# compiegne_v2.net
KiCad netlist of a schematic drawn in EAGLE
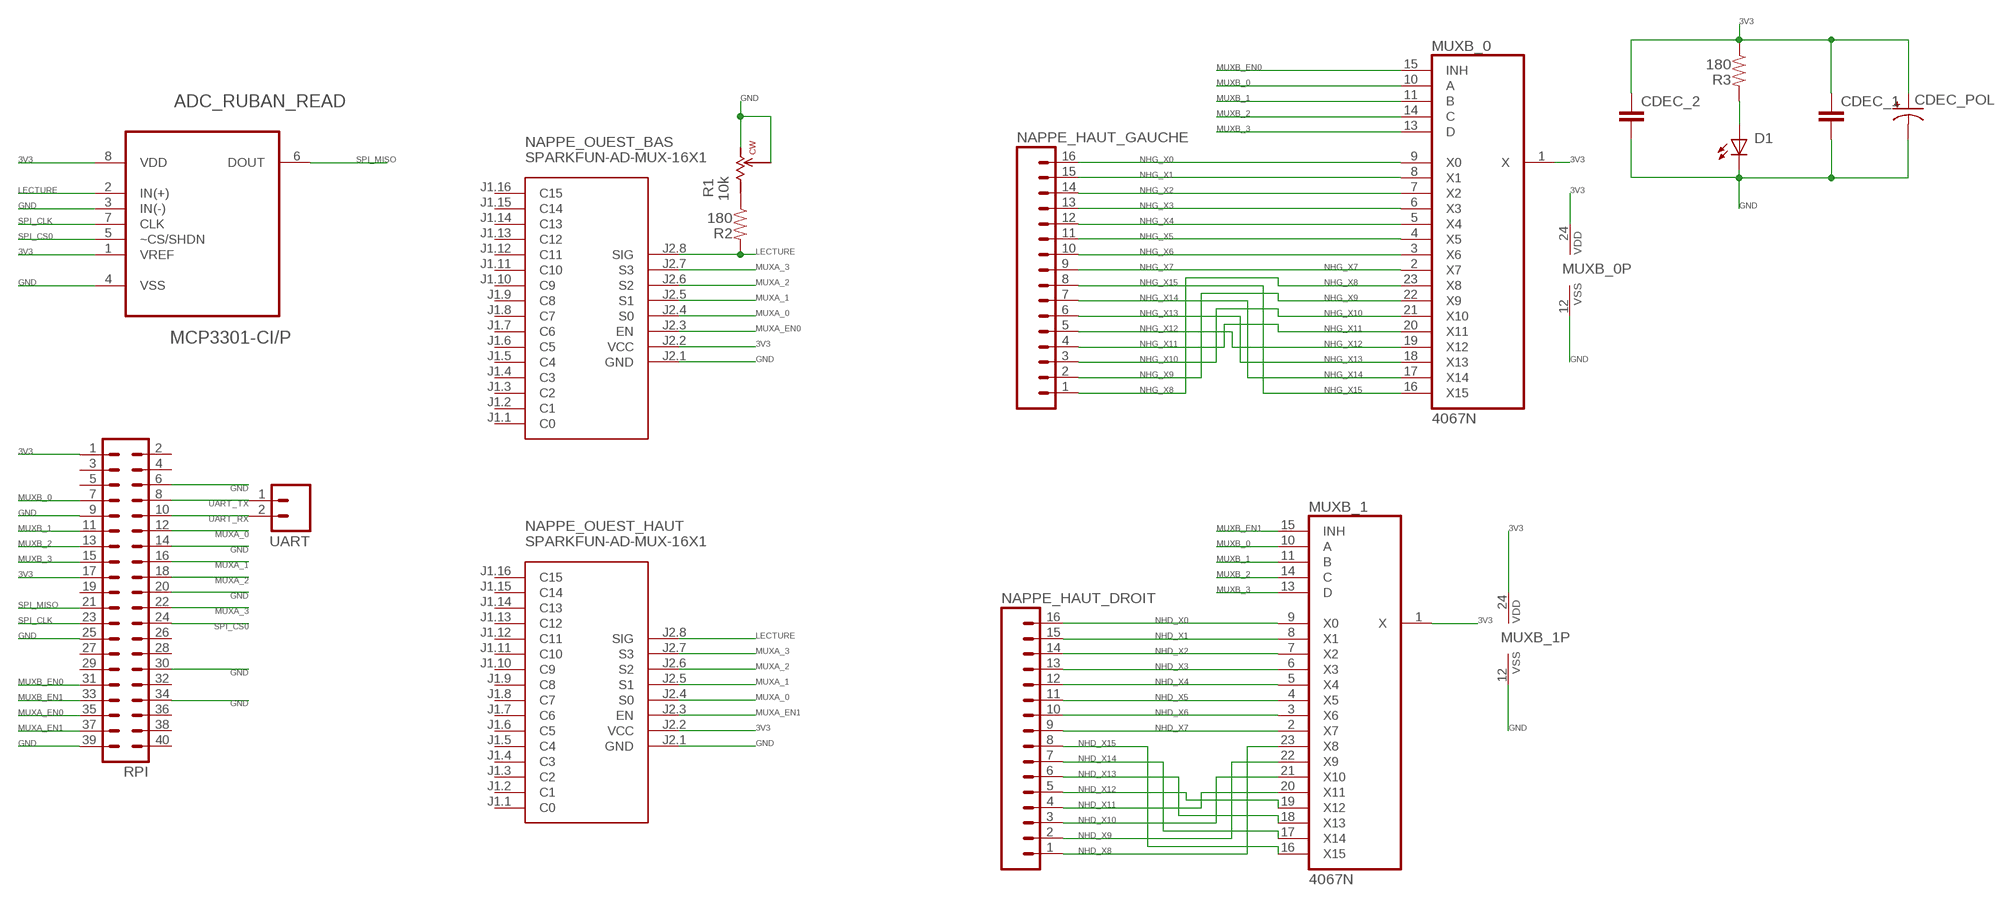
[diagram p0: schematic, sheet 1]

(export (version "E")
  (design (tool "Eeschema 10.0.6"))
  (components
    (comp (ref "ADC_RUBAN_READ")
      (value "MCP3301-CI/P")
      (footprint "eagle-import:DIP254P762X432-8")
      (libsource (lib "eagle-import") (part "MCP3301-CI/P"))
    )
    (comp (ref "CDEC_1")
      (value "PASSIF-CAP-PTH")
      (footprint "eagle-import:CAP-PTH")
      (libsource (lib "eagle-import") (part "PASSIF-CAP-PTH"))
    )
    (comp (ref "CDEC_2")
      (value "PASSIF-CAP-PTH")
      (footprint "eagle-import:CAP-PTH")
      (libsource (lib "eagle-import") (part "PASSIF-CAP-PTH"))
    )
    (comp (ref "CDEC_POL")
      (value "PASSIF-CAP_POL-TANTALUM-PTH")
      (footprint "eagle-import:CAP_POL-TANTALUM-PTH")
      (libsource (lib "eagle-import") (part "PASSIF-CAP_POL-TANTALUM-PTH"))
    )
    (comp (ref "D1")
      (value "LED-3MM")
      (footprint "eagle-import:3MM-LED")
      (libsource (lib "eagle-import") (part "LED-3MM"))
    )
    (comp (ref "MUXB_0")
      (value "4067N")
      (footprint "eagle-import:DIL24-6")
      (libsource (lib "eagle-import") (part "4067N"))
    )
    (comp (ref "MUXB_1")
      (value "4067N")
      (footprint "eagle-import:DIL24-6")
      (libsource (lib "eagle-import") (part "4067N"))
    )
    (comp (ref "NAPPE_HAUT_DROIT")
      (value "MA16")
      (footprint "eagle-import:16PA")
      (libsource (lib "eagle-import") (part "MA16"))
    )
    (comp (ref "NAPPE_HAUT_GAUCHE")
      (value "MA16")
      (footprint "eagle-import:16PA")
      (libsource (lib "eagle-import") (part "MA16"))
    )
    (comp (ref "NAPPE_OUEST_BAS")
      (value "SPARKFUN-AD-MUX-16X1")
      (footprint "eagle-import:SPARKFUN-AD-MUX-16X1")
      (libsource (lib "eagle-import") (part "SPARKFUN-AD-MUX-16X1"))
    )
    (comp (ref "NAPPE_OUEST_HAUT")
      (value "SPARKFUN-AD-MUX-16X1")
      (footprint "eagle-import:SPARKFUN-AD-MUX-16X1")
      (libsource (lib "eagle-import") (part "SPARKFUN-AD-MUX-16X1"))
    )
    (comp (ref "R1")
      (value "10k")
      (footprint "eagle-import:TRIMPOT_3266")
      (libsource (lib "eagle-import") (part "TRIMPOT_3266"))
    )
    (comp (ref "R2")
      (value "180")
      (footprint "eagle-import:RESISTOR-PTH")
      (libsource (lib "eagle-import") (part "PASSIF-RESISTOR-PTH"))
    )
    (comp (ref "R3")
      (value "180")
      (footprint "eagle-import:RESISTOR-PTH")
      (libsource (lib "eagle-import") (part "PASSIF-RESISTOR-PTH"))
    )
    (comp (ref "RPI")
      (value "MA20-2")
      (footprint "eagle-import:MA20-2")
      (libsource (lib "eagle-import") (part "MA20-2"))
    )
    (comp (ref "UART")
      (value "MA02")
      (footprint "eagle-import:02PA")
      (libsource (lib "eagle-import") (part "MA02"))
    )
  )
  (nets
    (net (code "1") (name "/3V3") (class "Default")
      (node (ref "ADC_RUBAN_READ") (pin "1") (pinfunction "VREF_1") (pintype "input"))
      (node (ref "ADC_RUBAN_READ") (pin "8") (pinfunction "VDD_8") (pintype "power_in"))
      (node (ref "CDEC_1") (pin "P$1") (pinfunction "1_P$1") (pintype "passive"))
      (node (ref "CDEC_2") (pin "P$1") (pinfunction "1_P$1") (pintype "passive"))
      (node (ref "CDEC_POL") (pin "+") (pinfunction "+_+") (pintype "passive"))
      (node (ref "MUXB_0") (pin "1") (pinfunction "X_1") (pintype "output"))
      (node (ref "MUXB_0") (pin "24") (pinfunction "VDD_24") (pintype "power_in"))
      (node (ref "MUXB_1") (pin "1") (pinfunction "X_1") (pintype "output"))
      (node (ref "MUXB_1") (pin "24") (pinfunction "VDD_24") (pintype "power_in"))
      (node (ref "NAPPE_OUEST_BAS") (pin "J2.2") (pinfunction "VCC_J2.2") (pintype "power_in"))
      (node (ref "NAPPE_OUEST_HAUT") (pin "J2.2") (pinfunction "VCC_J2.2") (pintype "power_in"))
      (node (ref "R3") (pin "P$1") (pinfunction "1_P$1") (pintype "passive"))
      (node (ref "RPI") (pin "1") (pinfunction "1_1") (pintype "passive"))
      (node (ref "RPI") (pin "17") (pinfunction "17_17") (pintype "passive"))
    )
    (net (code "2") (name "/GND") (class "Default")
      (node (ref "ADC_RUBAN_READ") (pin "3") (pinfunction "IN(-)_3") (pintype "input"))
      (node (ref "ADC_RUBAN_READ") (pin "4") (pinfunction "VSS_4") (pintype "passive"))
      (node (ref "CDEC_1") (pin "P$2") (pinfunction "2_P$2") (pintype "passive"))
      (node (ref "CDEC_2") (pin "P$2") (pinfunction "2_P$2") (pintype "passive"))
      (node (ref "CDEC_POL") (pin "-") (pinfunction "-_-") (pintype "passive"))
      (node (ref "D1") (pin "C") (pinfunction "C_C") (pintype "passive"))
      (node (ref "MUXB_0") (pin "12") (pinfunction "VSS_12") (pintype "power_in"))
      (node (ref "MUXB_1") (pin "12") (pinfunction "VSS_12") (pintype "power_in"))
      (node (ref "NAPPE_OUEST_BAS") (pin "J2.1") (pinfunction "GND_J2.1") (pintype "power_in"))
      (node (ref "NAPPE_OUEST_HAUT") (pin "J2.1") (pinfunction "GND_J2.1") (pintype "power_in"))
      (node (ref "R1") (pin "2") (pinfunction "2_2") (pintype "passive"))
      (node (ref "R1") (pin "3") (pinfunction "3_3") (pintype "passive"))
      (node (ref "RPI") (pin "14") (pinfunction "14_14") (pintype "passive"))
      (node (ref "RPI") (pin "20") (pinfunction "20_20") (pintype "passive"))
      (node (ref "RPI") (pin "25") (pinfunction "25_25") (pintype "passive"))
      (node (ref "RPI") (pin "30") (pinfunction "30_30") (pintype "passive"))
      (node (ref "RPI") (pin "34") (pinfunction "34_34") (pintype "passive"))
      (node (ref "RPI") (pin "39") (pinfunction "39_39") (pintype "passive"))
      (node (ref "RPI") (pin "6") (pinfunction "6_6") (pintype "passive"))
      (node (ref "RPI") (pin "9") (pinfunction "9_9") (pintype "passive"))
    )
    (net (code "3") (name "/LECTURE") (class "Default")
      (node (ref "ADC_RUBAN_READ") (pin "2") (pinfunction "IN(+)_2") (pintype "input"))
      (node (ref "NAPPE_OUEST_BAS") (pin "J2.8") (pinfunction "SIG_J2.8") (pintype "bidirectional"))
      (node (ref "NAPPE_OUEST_HAUT") (pin "J2.8") (pinfunction "SIG_J2.8") (pintype "bidirectional"))
      (node (ref "R2") (pin "P$2") (pinfunction "2_P$2") (pintype "passive"))
    )
    (net (code "4") (name "/MUXA_0") (class "Default")
      (node (ref "NAPPE_OUEST_BAS") (pin "J2.4") (pinfunction "S0_J2.4") (pintype "bidirectional"))
      (node (ref "NAPPE_OUEST_HAUT") (pin "J2.4") (pinfunction "S0_J2.4") (pintype "bidirectional"))
      (node (ref "RPI") (pin "12") (pinfunction "12_12") (pintype "passive"))
    )
    (net (code "5") (name "/MUXA_1") (class "Default")
      (node (ref "NAPPE_OUEST_BAS") (pin "J2.5") (pinfunction "S1_J2.5") (pintype "bidirectional"))
      (node (ref "NAPPE_OUEST_HAUT") (pin "J2.5") (pinfunction "S1_J2.5") (pintype "bidirectional"))
      (node (ref "RPI") (pin "16") (pinfunction "16_16") (pintype "passive"))
    )
    (net (code "6") (name "/MUXA_2") (class "Default")
      (node (ref "NAPPE_OUEST_BAS") (pin "J2.6") (pinfunction "S2_J2.6") (pintype "bidirectional"))
      (node (ref "NAPPE_OUEST_HAUT") (pin "J2.6") (pinfunction "S2_J2.6") (pintype "bidirectional"))
      (node (ref "RPI") (pin "18") (pinfunction "18_18") (pintype "passive"))
    )
    (net (code "7") (name "/MUXA_3") (class "Default")
      (node (ref "NAPPE_OUEST_BAS") (pin "J2.7") (pinfunction "S3_J2.7") (pintype "bidirectional"))
      (node (ref "NAPPE_OUEST_HAUT") (pin "J2.7") (pinfunction "S3_J2.7") (pintype "bidirectional"))
      (node (ref "RPI") (pin "22") (pinfunction "22_22") (pintype "passive"))
    )
    (net (code "8") (name "/MUXA_EN0") (class "Default")
      (node (ref "NAPPE_OUEST_BAS") (pin "J2.3") (pinfunction "EN_J2.3") (pintype "input"))
      (node (ref "RPI") (pin "35") (pinfunction "35_35") (pintype "passive"))
    )
    (net (code "9") (name "/MUXA_EN1") (class "Default")
      (node (ref "NAPPE_OUEST_HAUT") (pin "J2.3") (pinfunction "EN_J2.3") (pintype "input"))
      (node (ref "RPI") (pin "37") (pinfunction "37_37") (pintype "passive"))
    )
    (net (code "10") (name "/MUXB_0") (class "Default")
      (node (ref "MUXB_0") (pin "10") (pinfunction "A_10") (pintype "input"))
      (node (ref "MUXB_1") (pin "10") (pinfunction "A_10") (pintype "input"))
      (node (ref "RPI") (pin "7") (pinfunction "7_7") (pintype "passive"))
    )
    (net (code "11") (name "/MUXB_1") (class "Default")
      (node (ref "MUXB_0") (pin "11") (pinfunction "B_11") (pintype "input"))
      (node (ref "MUXB_1") (pin "11") (pinfunction "B_11") (pintype "input"))
      (node (ref "RPI") (pin "11") (pinfunction "11_11") (pintype "passive"))
    )
    (net (code "12") (name "/MUXB_2") (class "Default")
      (node (ref "MUXB_0") (pin "14") (pinfunction "C_14") (pintype "input"))
      (node (ref "MUXB_1") (pin "14") (pinfunction "C_14") (pintype "input"))
      (node (ref "RPI") (pin "13") (pinfunction "13_13") (pintype "passive"))
    )
    (net (code "13") (name "/MUXB_3") (class "Default")
      (node (ref "MUXB_0") (pin "13") (pinfunction "D_13") (pintype "input"))
      (node (ref "MUXB_1") (pin "13") (pinfunction "D_13") (pintype "input"))
      (node (ref "RPI") (pin "15") (pinfunction "15_15") (pintype "passive"))
    )
    (net (code "14") (name "/MUXB_EN0") (class "Default")
      (node (ref "MUXB_0") (pin "15") (pinfunction "INH_15") (pintype "input"))
      (node (ref "RPI") (pin "31") (pinfunction "31_31") (pintype "passive"))
    )
    (net (code "15") (name "/MUXB_EN1") (class "Default")
      (node (ref "MUXB_1") (pin "15") (pinfunction "INH_15") (pintype "input"))
      (node (ref "RPI") (pin "33") (pinfunction "33_33") (pintype "passive"))
    )
    (net (code "16") (name "/NHD_X0") (class "Default")
      (node (ref "MUXB_1") (pin "9") (pinfunction "X0_9") (pintype "input"))
      (node (ref "NAPPE_HAUT_DROIT") (pin "16") (pinfunction "16_16") (pintype "passive"))
    )
    (net (code "17") (name "/NHD_X1") (class "Default")
      (node (ref "MUXB_1") (pin "8") (pinfunction "X1_8") (pintype "input"))
      (node (ref "NAPPE_HAUT_DROIT") (pin "15") (pinfunction "15_15") (pintype "passive"))
    )
    (net (code "18") (name "/NHD_X2") (class "Default")
      (node (ref "MUXB_1") (pin "7") (pinfunction "X2_7") (pintype "input"))
      (node (ref "NAPPE_HAUT_DROIT") (pin "14") (pinfunction "14_14") (pintype "passive"))
    )
    (net (code "19") (name "/NHD_X3") (class "Default")
      (node (ref "MUXB_1") (pin "6") (pinfunction "X3_6") (pintype "input"))
      (node (ref "NAPPE_HAUT_DROIT") (pin "13") (pinfunction "13_13") (pintype "passive"))
    )
    (net (code "20") (name "/NHD_X4") (class "Default")
      (node (ref "MUXB_1") (pin "5") (pinfunction "X4_5") (pintype "input"))
      (node (ref "NAPPE_HAUT_DROIT") (pin "12") (pinfunction "12_12") (pintype "passive"))
    )
    (net (code "21") (name "/NHD_X5") (class "Default")
      (node (ref "MUXB_1") (pin "4") (pinfunction "X5_4") (pintype "input"))
      (node (ref "NAPPE_HAUT_DROIT") (pin "11") (pinfunction "11_11") (pintype "passive"))
    )
    (net (code "22") (name "/NHD_X6") (class "Default")
      (node (ref "MUXB_1") (pin "3") (pinfunction "X6_3") (pintype "input"))
      (node (ref "NAPPE_HAUT_DROIT") (pin "10") (pinfunction "10_10") (pintype "passive"))
    )
    (net (code "23") (name "/NHD_X7") (class "Default")
      (node (ref "MUXB_1") (pin "2") (pinfunction "X7_2") (pintype "input"))
      (node (ref "NAPPE_HAUT_DROIT") (pin "9") (pinfunction "9_9") (pintype "passive"))
    )
    (net (code "24") (name "/NHD_X8") (class "Default")
      (node (ref "MUXB_1") (pin "23") (pinfunction "X8_23") (pintype "input"))
      (node (ref "NAPPE_HAUT_DROIT") (pin "1") (pinfunction "1_1") (pintype "passive"))
    )
    (net (code "25") (name "/NHD_X9") (class "Default")
      (node (ref "MUXB_1") (pin "22") (pinfunction "X9_22") (pintype "input"))
      (node (ref "NAPPE_HAUT_DROIT") (pin "2") (pinfunction "2_2") (pintype "passive"))
    )
    (net (code "26") (name "/NHD_X10") (class "Default")
      (node (ref "MUXB_1") (pin "21") (pinfunction "X10_21") (pintype "input"))
      (node (ref "NAPPE_HAUT_DROIT") (pin "3") (pinfunction "3_3") (pintype "passive"))
    )
    (net (code "27") (name "/NHD_X11") (class "Default")
      (node (ref "MUXB_1") (pin "20") (pinfunction "X11_20") (pintype "input"))
      (node (ref "NAPPE_HAUT_DROIT") (pin "4") (pinfunction "4_4") (pintype "passive"))
    )
    (net (code "28") (name "/NHD_X12") (class "Default")
      (node (ref "MUXB_1") (pin "19") (pinfunction "X12_19") (pintype "input"))
      (node (ref "NAPPE_HAUT_DROIT") (pin "5") (pinfunction "5_5") (pintype "passive"))
    )
    (net (code "29") (name "/NHD_X13") (class "Default")
      (node (ref "MUXB_1") (pin "18") (pinfunction "X13_18") (pintype "input"))
      (node (ref "NAPPE_HAUT_DROIT") (pin "6") (pinfunction "6_6") (pintype "passive"))
    )
    (net (code "30") (name "/NHD_X14") (class "Default")
      (node (ref "MUXB_1") (pin "17") (pinfunction "X14_17") (pintype "input"))
      (node (ref "NAPPE_HAUT_DROIT") (pin "7") (pinfunction "7_7") (pintype "passive"))
    )
    (net (code "31") (name "/NHD_X15") (class "Default")
      (node (ref "MUXB_1") (pin "16") (pinfunction "X15_16") (pintype "input"))
      (node (ref "NAPPE_HAUT_DROIT") (pin "8") (pinfunction "8_8") (pintype "passive"))
    )
    (net (code "32") (name "/NHG_X0") (class "Default")
      (node (ref "MUXB_0") (pin "9") (pinfunction "X0_9") (pintype "input"))
      (node (ref "NAPPE_HAUT_GAUCHE") (pin "16") (pinfunction "16_16") (pintype "passive"))
    )
    (net (code "33") (name "/NHG_X1") (class "Default")
      (node (ref "MUXB_0") (pin "8") (pinfunction "X1_8") (pintype "input"))
      (node (ref "NAPPE_HAUT_GAUCHE") (pin "15") (pinfunction "15_15") (pintype "passive"))
    )
    (net (code "34") (name "/NHG_X2") (class "Default")
      (node (ref "MUXB_0") (pin "7") (pinfunction "X2_7") (pintype "input"))
      (node (ref "NAPPE_HAUT_GAUCHE") (pin "14") (pinfunction "14_14") (pintype "passive"))
    )
    (net (code "35") (name "/NHG_X3") (class "Default")
      (node (ref "MUXB_0") (pin "6") (pinfunction "X3_6") (pintype "input"))
      (node (ref "NAPPE_HAUT_GAUCHE") (pin "13") (pinfunction "13_13") (pintype "passive"))
    )
    (net (code "36") (name "/NHG_X4") (class "Default")
      (node (ref "MUXB_0") (pin "5") (pinfunction "X4_5") (pintype "input"))
      (node (ref "NAPPE_HAUT_GAUCHE") (pin "12") (pinfunction "12_12") (pintype "passive"))
    )
    (net (code "37") (name "/NHG_X5") (class "Default")
      (node (ref "MUXB_0") (pin "4") (pinfunction "X5_4") (pintype "input"))
      (node (ref "NAPPE_HAUT_GAUCHE") (pin "11") (pinfunction "11_11") (pintype "passive"))
    )
    (net (code "38") (name "/NHG_X6") (class "Default")
      (node (ref "MUXB_0") (pin "3") (pinfunction "X6_3") (pintype "input"))
      (node (ref "NAPPE_HAUT_GAUCHE") (pin "10") (pinfunction "10_10") (pintype "passive"))
    )
    (net (code "39") (name "/NHG_X7") (class "Default")
      (node (ref "MUXB_0") (pin "2") (pinfunction "X7_2") (pintype "input"))
      (node (ref "NAPPE_HAUT_GAUCHE") (pin "9") (pinfunction "9_9") (pintype "passive"))
    )
    (net (code "40") (name "/NHG_X8") (class "Default")
      (node (ref "MUXB_0") (pin "23") (pinfunction "X8_23") (pintype "input"))
      (node (ref "NAPPE_HAUT_GAUCHE") (pin "1") (pinfunction "1_1") (pintype "passive"))
    )
    (net (code "41") (name "/NHG_X9") (class "Default")
      (node (ref "MUXB_0") (pin "22") (pinfunction "X9_22") (pintype "input"))
      (node (ref "NAPPE_HAUT_GAUCHE") (pin "2") (pinfunction "2_2") (pintype "passive"))
    )
    (net (code "42") (name "/NHG_X10") (class "Default")
      (node (ref "MUXB_0") (pin "21") (pinfunction "X10_21") (pintype "input"))
      (node (ref "NAPPE_HAUT_GAUCHE") (pin "3") (pinfunction "3_3") (pintype "passive"))
    )
    (net (code "43") (name "/NHG_X11") (class "Default")
      (node (ref "MUXB_0") (pin "20") (pinfunction "X11_20") (pintype "input"))
      (node (ref "NAPPE_HAUT_GAUCHE") (pin "4") (pinfunction "4_4") (pintype "passive"))
    )
    (net (code "44") (name "/NHG_X12") (class "Default")
      (node (ref "MUXB_0") (pin "19") (pinfunction "X12_19") (pintype "input"))
      (node (ref "NAPPE_HAUT_GAUCHE") (pin "5") (pinfunction "5_5") (pintype "passive"))
    )
    (net (code "45") (name "/NHG_X13") (class "Default")
      (node (ref "MUXB_0") (pin "18") (pinfunction "X13_18") (pintype "input"))
      (node (ref "NAPPE_HAUT_GAUCHE") (pin "6") (pinfunction "6_6") (pintype "passive"))
    )
    (net (code "46") (name "/NHG_X14") (class "Default")
      (node (ref "MUXB_0") (pin "17") (pinfunction "X14_17") (pintype "input"))
      (node (ref "NAPPE_HAUT_GAUCHE") (pin "7") (pinfunction "7_7") (pintype "passive"))
    )
    (net (code "47") (name "/NHG_X15") (class "Default")
      (node (ref "MUXB_0") (pin "16") (pinfunction "X15_16") (pintype "input"))
      (node (ref "NAPPE_HAUT_GAUCHE") (pin "8") (pinfunction "8_8") (pintype "passive"))
    )
    (net (code "48") (name "/SPI_CLK") (class "Default")
      (node (ref "ADC_RUBAN_READ") (pin "7") (pinfunction "CLK_7") (pintype "input"))
      (node (ref "RPI") (pin "23") (pinfunction "23_23") (pintype "passive"))
    )
    (net (code "49") (name "/SPI_CS0") (class "Default")
      (node (ref "ADC_RUBAN_READ") (pin "5") (pinfunction "~{CS/SHDN}_5") (pintype "input"))
      (node (ref "RPI") (pin "24") (pinfunction "24_24") (pintype "passive"))
    )
    (net (code "50") (name "/SPI_MISO") (class "Default")
      (node (ref "ADC_RUBAN_READ") (pin "6") (pinfunction "DOUT_6") (pintype "output"))
      (node (ref "RPI") (pin "21") (pinfunction "21_21") (pintype "passive"))
    )
    (net (code "51") (name "/UART_RX") (class "Default")
      (node (ref "RPI") (pin "10") (pinfunction "10_10") (pintype "passive"))
      (node (ref "UART") (pin "2") (pinfunction "2_2") (pintype "passive"))
    )
    (net (code "52") (name "/UART_TX") (class "Default")
      (node (ref "RPI") (pin "8") (pinfunction "8_8") (pintype "passive"))
      (node (ref "UART") (pin "1") (pinfunction "1_1") (pintype "passive"))
    )
    (net (code "53") (name "Net-(R2-1)") (class "Default")
      (node (ref "R1") (pin "1") (pinfunction "1_1") (pintype "passive"))
      (node (ref "R2") (pin "P$1") (pinfunction "1_P$1") (pintype "passive"))
    )
    (net (code "54") (name "Net-(R3-2)") (class "Default")
      (node (ref "D1") (pin "A") (pinfunction "A_A") (pintype "passive"))
      (node (ref "R3") (pin "P$2") (pinfunction "2_P$2") (pintype "passive"))
    )
    (net (code "55") (name "unconnected-(NAPPE_OUEST_BAS-C0-PadJ1.1)") (class "Default")
      (node (ref "NAPPE_OUEST_BAS") (pin "J1.1") (pinfunction "C0_J1.1") (pintype "bidirectional"))
    )
    (net (code "56") (name "unconnected-(NAPPE_OUEST_BAS-C1-PadJ1.2)") (class "Default")
      (node (ref "NAPPE_OUEST_BAS") (pin "J1.2") (pinfunction "C1_J1.2") (pintype "bidirectional"))
    )
    (net (code "57") (name "unconnected-(NAPPE_OUEST_BAS-C2-PadJ1.3)") (class "Default")
      (node (ref "NAPPE_OUEST_BAS") (pin "J1.3") (pinfunction "C2_J1.3") (pintype "bidirectional"))
    )
    (net (code "58") (name "unconnected-(NAPPE_OUEST_BAS-C3-PadJ1.4)") (class "Default")
      (node (ref "NAPPE_OUEST_BAS") (pin "J1.4") (pinfunction "C3_J1.4") (pintype "bidirectional"))
    )
    (net (code "59") (name "unconnected-(NAPPE_OUEST_BAS-C4-PadJ1.5)") (class "Default")
      (node (ref "NAPPE_OUEST_BAS") (pin "J1.5") (pinfunction "C4_J1.5") (pintype "bidirectional"))
    )
    (net (code "60") (name "unconnected-(NAPPE_OUEST_BAS-C5-PadJ1.6)") (class "Default")
      (node (ref "NAPPE_OUEST_BAS") (pin "J1.6") (pinfunction "C5_J1.6") (pintype "bidirectional"))
    )
    (net (code "61") (name "unconnected-(NAPPE_OUEST_BAS-C6-PadJ1.7)") (class "Default")
      (node (ref "NAPPE_OUEST_BAS") (pin "J1.7") (pinfunction "C6_J1.7") (pintype "bidirectional"))
    )
    (net (code "62") (name "unconnected-(NAPPE_OUEST_BAS-C7-PadJ1.8)") (class "Default")
      (node (ref "NAPPE_OUEST_BAS") (pin "J1.8") (pinfunction "C7_J1.8") (pintype "bidirectional"))
    )
    (net (code "63") (name "unconnected-(NAPPE_OUEST_BAS-C8-PadJ1.9)") (class "Default")
      (node (ref "NAPPE_OUEST_BAS") (pin "J1.9") (pinfunction "C8_J1.9") (pintype "bidirectional"))
    )
    (net (code "64") (name "unconnected-(NAPPE_OUEST_BAS-C9-PadJ1.10)") (class "Default")
      (node (ref "NAPPE_OUEST_BAS") (pin "J1.10") (pinfunction "C9_J1.10") (pintype "bidirectional"))
    )
    (net (code "65") (name "unconnected-(NAPPE_OUEST_BAS-C10-PadJ1.11)") (class "Default")
      (node (ref "NAPPE_OUEST_BAS") (pin "J1.11") (pinfunction "C10_J1.11") (pintype "bidirectional"))
    )
    (net (code "66") (name "unconnected-(NAPPE_OUEST_BAS-C11-PadJ1.12)") (class "Default")
      (node (ref "NAPPE_OUEST_BAS") (pin "J1.12") (pinfunction "C11_J1.12") (pintype "bidirectional"))
    )
    (net (code "67") (name "unconnected-(NAPPE_OUEST_BAS-C12-PadJ1.13)") (class "Default")
      (node (ref "NAPPE_OUEST_BAS") (pin "J1.13") (pinfunction "C12_J1.13") (pintype "bidirectional"))
    )
    (net (code "68") (name "unconnected-(NAPPE_OUEST_BAS-C13-PadJ1.14)") (class "Default")
      (node (ref "NAPPE_OUEST_BAS") (pin "J1.14") (pinfunction "C13_J1.14") (pintype "bidirectional"))
    )
    (net (code "69") (name "unconnected-(NAPPE_OUEST_BAS-C14-PadJ1.15)") (class "Default")
      (node (ref "NAPPE_OUEST_BAS") (pin "J1.15") (pinfunction "C14_J1.15") (pintype "bidirectional"))
    )
    (net (code "70") (name "unconnected-(NAPPE_OUEST_BAS-C15-PadJ1.16)") (class "Default")
      (node (ref "NAPPE_OUEST_BAS") (pin "J1.16") (pinfunction "C15_J1.16") (pintype "bidirectional"))
    )
    (net (code "71") (name "unconnected-(NAPPE_OUEST_HAUT-C0-PadJ1.1)") (class "Default")
      (node (ref "NAPPE_OUEST_HAUT") (pin "J1.1") (pinfunction "C0_J1.1") (pintype "bidirectional"))
    )
    (net (code "72") (name "unconnected-(NAPPE_OUEST_HAUT-C1-PadJ1.2)") (class "Default")
      (node (ref "NAPPE_OUEST_HAUT") (pin "J1.2") (pinfunction "C1_J1.2") (pintype "bidirectional"))
    )
    (net (code "73") (name "unconnected-(NAPPE_OUEST_HAUT-C2-PadJ1.3)") (class "Default")
      (node (ref "NAPPE_OUEST_HAUT") (pin "J1.3") (pinfunction "C2_J1.3") (pintype "bidirectional"))
    )
    (net (code "74") (name "unconnected-(NAPPE_OUEST_HAUT-C3-PadJ1.4)") (class "Default")
      (node (ref "NAPPE_OUEST_HAUT") (pin "J1.4") (pinfunction "C3_J1.4") (pintype "bidirectional"))
    )
    (net (code "75") (name "unconnected-(NAPPE_OUEST_HAUT-C4-PadJ1.5)") (class "Default")
      (node (ref "NAPPE_OUEST_HAUT") (pin "J1.5") (pinfunction "C4_J1.5") (pintype "bidirectional"))
    )
    (net (code "76") (name "unconnected-(NAPPE_OUEST_HAUT-C5-PadJ1.6)") (class "Default")
      (node (ref "NAPPE_OUEST_HAUT") (pin "J1.6") (pinfunction "C5_J1.6") (pintype "bidirectional"))
    )
    (net (code "77") (name "unconnected-(NAPPE_OUEST_HAUT-C6-PadJ1.7)") (class "Default")
      (node (ref "NAPPE_OUEST_HAUT") (pin "J1.7") (pinfunction "C6_J1.7") (pintype "bidirectional"))
    )
    (net (code "78") (name "unconnected-(NAPPE_OUEST_HAUT-C7-PadJ1.8)") (class "Default")
      (node (ref "NAPPE_OUEST_HAUT") (pin "J1.8") (pinfunction "C7_J1.8") (pintype "bidirectional"))
    )
    (net (code "79") (name "unconnected-(NAPPE_OUEST_HAUT-C8-PadJ1.9)") (class "Default")
      (node (ref "NAPPE_OUEST_HAUT") (pin "J1.9") (pinfunction "C8_J1.9") (pintype "bidirectional"))
    )
    (net (code "80") (name "unconnected-(NAPPE_OUEST_HAUT-C9-PadJ1.10)") (class "Default")
      (node (ref "NAPPE_OUEST_HAUT") (pin "J1.10") (pinfunction "C9_J1.10") (pintype "bidirectional"))
    )
    (net (code "81") (name "unconnected-(NAPPE_OUEST_HAUT-C10-PadJ1.11)") (class "Default")
      (node (ref "NAPPE_OUEST_HAUT") (pin "J1.11") (pinfunction "C10_J1.11") (pintype "bidirectional"))
    )
    (net (code "82") (name "unconnected-(NAPPE_OUEST_HAUT-C11-PadJ1.12)") (class "Default")
      (node (ref "NAPPE_OUEST_HAUT") (pin "J1.12") (pinfunction "C11_J1.12") (pintype "bidirectional"))
    )
    (net (code "83") (name "unconnected-(NAPPE_OUEST_HAUT-C12-PadJ1.13)") (class "Default")
      (node (ref "NAPPE_OUEST_HAUT") (pin "J1.13") (pinfunction "C12_J1.13") (pintype "bidirectional"))
    )
    (net (code "84") (name "unconnected-(NAPPE_OUEST_HAUT-C13-PadJ1.14)") (class "Default")
      (node (ref "NAPPE_OUEST_HAUT") (pin "J1.14") (pinfunction "C13_J1.14") (pintype "bidirectional"))
    )
    (net (code "85") (name "unconnected-(NAPPE_OUEST_HAUT-C14-PadJ1.15)") (class "Default")
      (node (ref "NAPPE_OUEST_HAUT") (pin "J1.15") (pinfunction "C14_J1.15") (pintype "bidirectional"))
    )
    (net (code "86") (name "unconnected-(NAPPE_OUEST_HAUT-C15-PadJ1.16)") (class "Default")
      (node (ref "NAPPE_OUEST_HAUT") (pin "J1.16") (pinfunction "C15_J1.16") (pintype "bidirectional"))
    )
    (net (code "87") (name "unconnected-(RPI-Pad2)") (class "Default")
      (node (ref "RPI") (pin "2") (pinfunction "2_2") (pintype "passive"))
    )
    (net (code "88") (name "unconnected-(RPI-Pad3)") (class "Default")
      (node (ref "RPI") (pin "3") (pinfunction "3_3") (pintype "passive"))
    )
    (net (code "89") (name "unconnected-(RPI-Pad4)") (class "Default")
      (node (ref "RPI") (pin "4") (pinfunction "4_4") (pintype "passive"))
    )
    (net (code "90") (name "unconnected-(RPI-Pad5)") (class "Default")
      (node (ref "RPI") (pin "5") (pinfunction "5_5") (pintype "passive"))
    )
    (net (code "91") (name "unconnected-(RPI-Pad19)") (class "Default")
      (node (ref "RPI") (pin "19") (pinfunction "19_19") (pintype "passive"))
    )
    (net (code "92") (name "unconnected-(RPI-Pad26)") (class "Default")
      (node (ref "RPI") (pin "26") (pinfunction "26_26") (pintype "passive"))
    )
    (net (code "93") (name "unconnected-(RPI-Pad27)") (class "Default")
      (node (ref "RPI") (pin "27") (pinfunction "27_27") (pintype "passive"))
    )
    (net (code "94") (name "unconnected-(RPI-Pad28)") (class "Default")
      (node (ref "RPI") (pin "28") (pinfunction "28_28") (pintype "passive"))
    )
    (net (code "95") (name "unconnected-(RPI-Pad29)") (class "Default")
      (node (ref "RPI") (pin "29") (pinfunction "29_29") (pintype "passive"))
    )
    (net (code "96") (name "unconnected-(RPI-Pad32)") (class "Default")
      (node (ref "RPI") (pin "32") (pinfunction "32_32") (pintype "passive"))
    )
    (net (code "97") (name "unconnected-(RPI-Pad36)") (class "Default")
      (node (ref "RPI") (pin "36") (pinfunction "36_36") (pintype "passive"))
    )
    (net (code "98") (name "unconnected-(RPI-Pad38)") (class "Default")
      (node (ref "RPI") (pin "38") (pinfunction "38_38") (pintype "passive"))
    )
    (net (code "99") (name "unconnected-(RPI-Pad40)") (class "Default")
      (node (ref "RPI") (pin "40") (pinfunction "40_40") (pintype "passive"))
    )
  )
)
